# Arria10_Power.net
KiCad netlist of a schematic drawn in Altium Designer
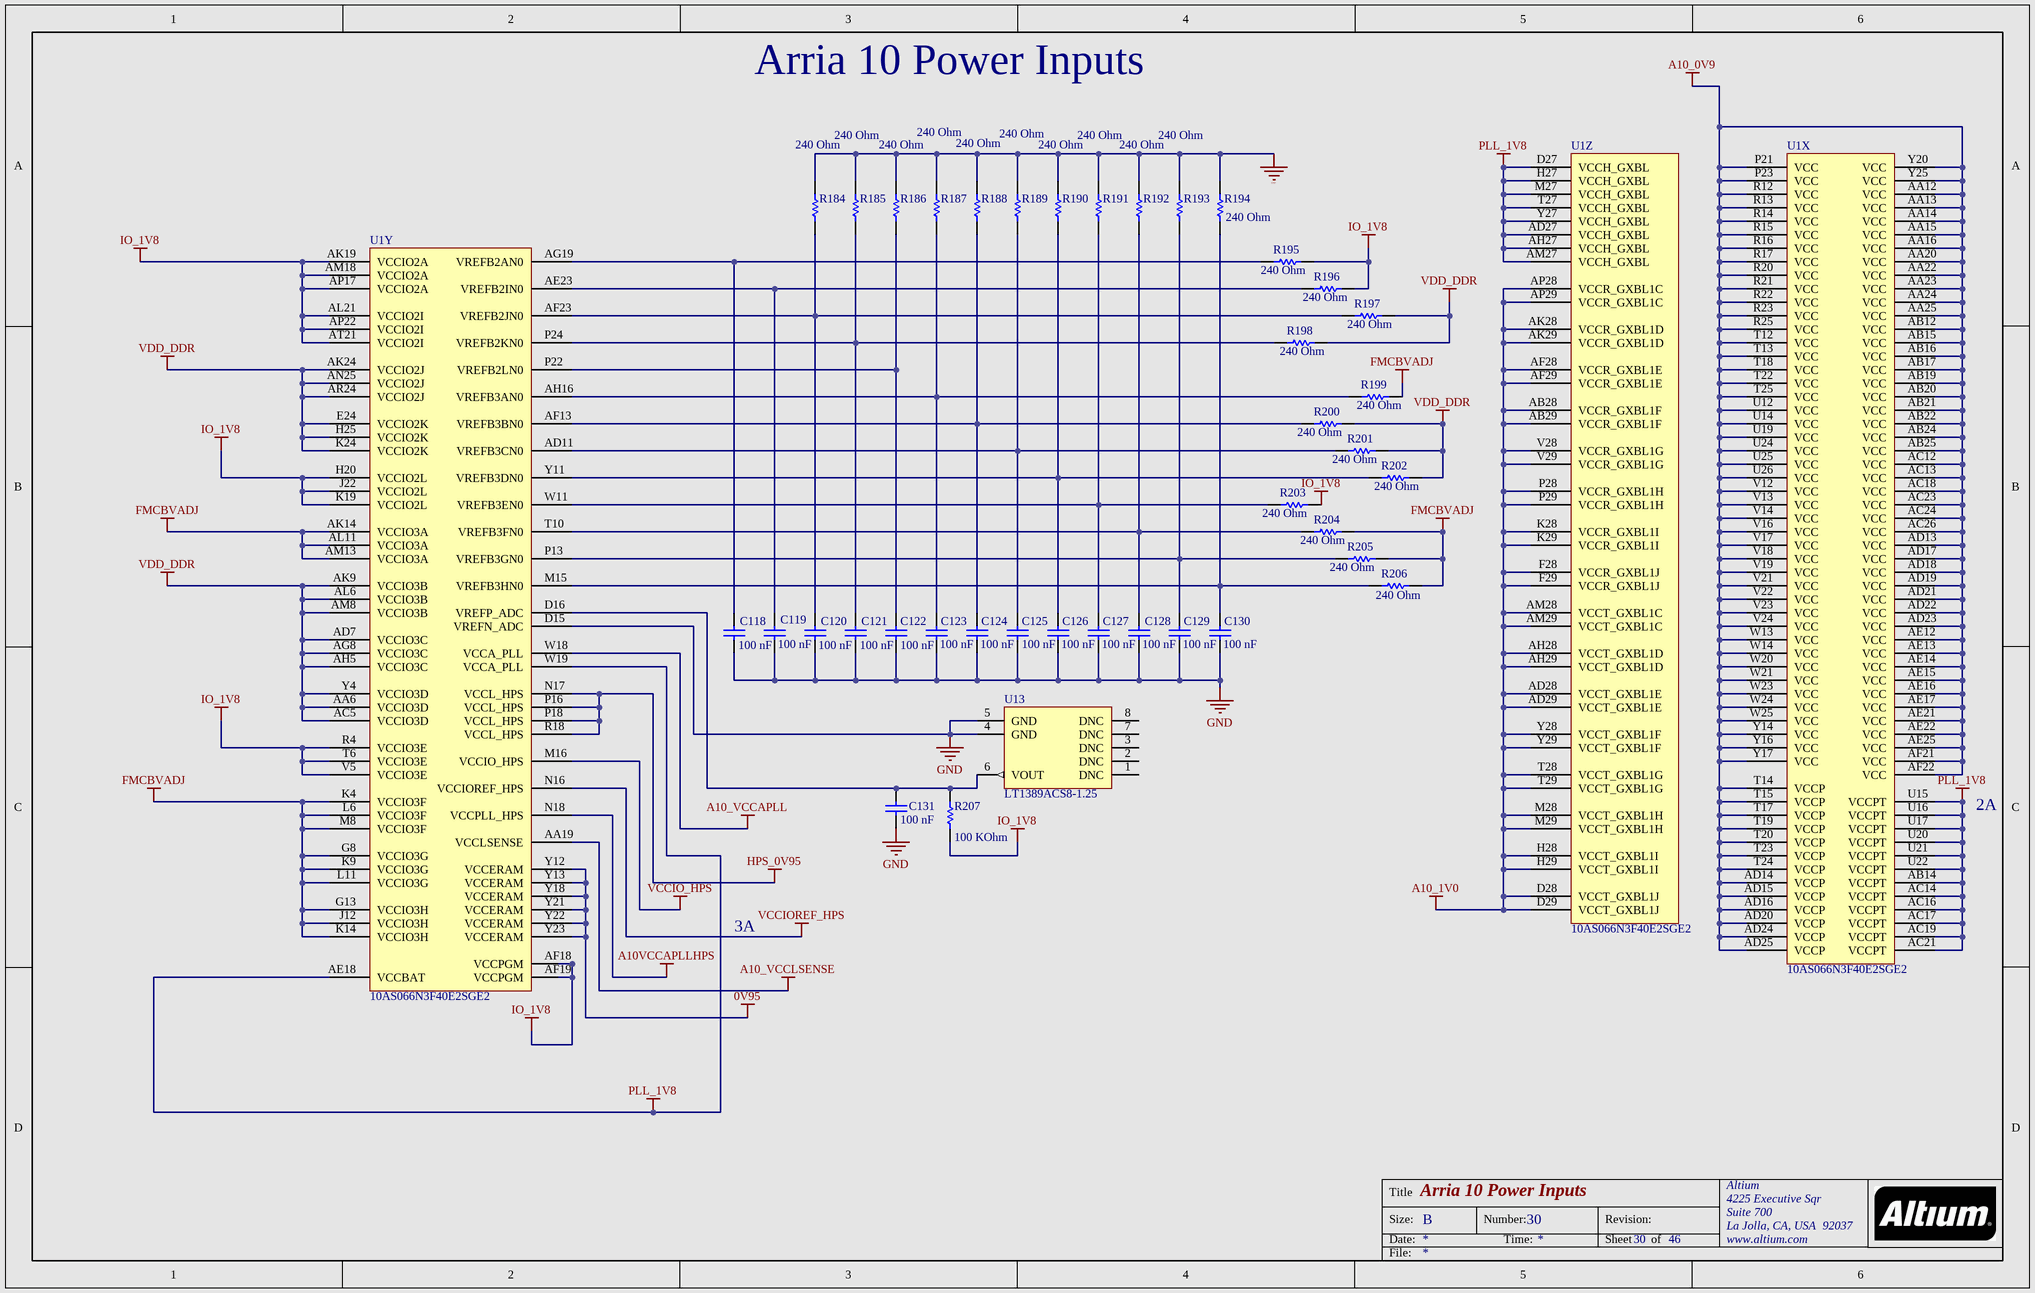
[diagram p0: Arria10_Power.SchDoc]

(export (version "E")
  (design (tool "Eeschema 10.0.6"))
  (components
    (comp (ref "C118")
      (value "GRM033R60J104KE19D")
      (footprint "CAPC0603X33X15LL03T05")
      (description "Chip Capacitor, 100 nF, +/- 10%, 6.3 V, -55 to 85 degC, 0201 (0603 Metric), RoHS, Tape and Reel")
      (fields
        (field (name "TOLERANCE") "10%")
        (field (name "CAPACITANCE") "100 nF")
        (field (name "MANUFACTURER") "Basic Passives")
      )
      (libsource (lib "Altium Content Vault") (part "CAP-NP-2"))
    )
    (comp (ref "C119")
      (value "GRM033R60J104KE19D")
      (footprint "CAPC0603X33X15LL03T05")
      (description "Chip Capacitor, 100 nF, +/- 10%, 6.3 V, -55 to 85 degC, 0201 (0603 Metric), RoHS, Tape and Reel")
      (fields
        (field (name "TOLERANCE") "10%")
        (field (name "CAPACITANCE") "100 nF")
        (field (name "MANUFACTURER") "Basic Passives")
      )
      (libsource (lib "Altium Content Vault") (part "CAP-NP-2"))
    )
    (comp (ref "C120")
      (value "GRM033R60J104KE19D")
      (footprint "CAPC0603X33X15LL03T05")
      (description "Chip Capacitor, 100 nF, +/- 10%, 6.3 V, -55 to 85 degC, 0201 (0603 Metric), RoHS, Tape and Reel")
      (fields
        (field (name "TOLERANCE") "10%")
        (field (name "CAPACITANCE") "100 nF")
        (field (name "MANUFACTURER") "Basic Passives")
      )
      (libsource (lib "Altium Content Vault") (part "CAP-NP-2"))
    )
    (comp (ref "C121")
      (value "GRM033R60J104KE19D")
      (footprint "CAPC0603X33X15LL03T05")
      (description "Chip Capacitor, 100 nF, +/- 10%, 6.3 V, -55 to 85 degC, 0201 (0603 Metric), RoHS, Tape and Reel")
      (fields
        (field (name "TOLERANCE") "10%")
        (field (name "CAPACITANCE") "100 nF")
        (field (name "MANUFACTURER") "Basic Passives")
      )
      (libsource (lib "Altium Content Vault") (part "CAP-NP-2"))
    )
    (comp (ref "C122")
      (value "GRM033R60J104KE19D")
      (footprint "CAPC0603X33X15LL03T05")
      (description "Chip Capacitor, 100 nF, +/- 10%, 6.3 V, -55 to 85 degC, 0201 (0603 Metric), RoHS, Tape and Reel")
      (fields
        (field (name "TOLERANCE") "10%")
        (field (name "CAPACITANCE") "100 nF")
        (field (name "MANUFACTURER") "Basic Passives")
      )
      (libsource (lib "Altium Content Vault") (part "CAP-NP-2"))
    )
    (comp (ref "C123")
      (value "GRM033R60J104KE19D")
      (footprint "CAPC0603X33X15LL03T05")
      (description "Chip Capacitor, 100 nF, +/- 10%, 6.3 V, -55 to 85 degC, 0201 (0603 Metric), RoHS, Tape and Reel")
      (fields
        (field (name "TOLERANCE") "10%")
        (field (name "CAPACITANCE") "100 nF")
        (field (name "MANUFACTURER") "Basic Passives")
      )
      (libsource (lib "Altium Content Vault") (part "CAP-NP-2"))
    )
    (comp (ref "C124")
      (value "GRM033R60J104KE19D")
      (footprint "CAPC0603X33X15LL03T05")
      (description "Chip Capacitor, 100 nF, +/- 10%, 6.3 V, -55 to 85 degC, 0201 (0603 Metric), RoHS, Tape and Reel")
      (fields
        (field (name "TOLERANCE") "10%")
        (field (name "CAPACITANCE") "100 nF")
        (field (name "MANUFACTURER") "Basic Passives")
      )
      (libsource (lib "Altium Content Vault") (part "CAP-NP-2"))
    )
    (comp (ref "C125")
      (value "GRM033R60J104KE19D")
      (footprint "CAPC0603X33X15LL03T05")
      (description "Chip Capacitor, 100 nF, +/- 10%, 6.3 V, -55 to 85 degC, 0201 (0603 Metric), RoHS, Tape and Reel")
      (fields
        (field (name "TOLERANCE") "10%")
        (field (name "CAPACITANCE") "100 nF")
        (field (name "MANUFACTURER") "Basic Passives")
      )
      (libsource (lib "Altium Content Vault") (part "CAP-NP-2"))
    )
    (comp (ref "C126")
      (value "GRM033R60J104KE19D")
      (footprint "CAPC0603X33X15LL03T05")
      (description "Chip Capacitor, 100 nF, +/- 10%, 6.3 V, -55 to 85 degC, 0201 (0603 Metric), RoHS, Tape and Reel")
      (fields
        (field (name "TOLERANCE") "10%")
        (field (name "CAPACITANCE") "100 nF")
        (field (name "MANUFACTURER") "Basic Passives")
      )
      (libsource (lib "Altium Content Vault") (part "CAP-NP-2"))
    )
    (comp (ref "C127")
      (value "GRM033R60J104KE19D")
      (footprint "CAPC0603X33X15LL03T05")
      (description "Chip Capacitor, 100 nF, +/- 10%, 6.3 V, -55 to 85 degC, 0201 (0603 Metric), RoHS, Tape and Reel")
      (fields
        (field (name "TOLERANCE") "10%")
        (field (name "CAPACITANCE") "100 nF")
        (field (name "MANUFACTURER") "Basic Passives")
      )
      (libsource (lib "Altium Content Vault") (part "CAP-NP-2"))
    )
    (comp (ref "C128")
      (value "GRM033R60J104KE19D")
      (footprint "CAPC0603X33X15LL03T05")
      (description "Chip Capacitor, 100 nF, +/- 10%, 6.3 V, -55 to 85 degC, 0201 (0603 Metric), RoHS, Tape and Reel")
      (fields
        (field (name "TOLERANCE") "10%")
        (field (name "CAPACITANCE") "100 nF")
        (field (name "MANUFACTURER") "Basic Passives")
      )
      (libsource (lib "Altium Content Vault") (part "CAP-NP-2"))
    )
    (comp (ref "C129")
      (value "GRM033R60J104KE19D")
      (footprint "CAPC0603X33X15LL03T05")
      (description "Chip Capacitor, 100 nF, +/- 10%, 6.3 V, -55 to 85 degC, 0201 (0603 Metric), RoHS, Tape and Reel")
      (fields
        (field (name "TOLERANCE") "10%")
        (field (name "CAPACITANCE") "100 nF")
        (field (name "MANUFACTURER") "Basic Passives")
      )
      (libsource (lib "Altium Content Vault") (part "CAP-NP-2"))
    )
    (comp (ref "C130")
      (value "GRM033R60J104KE19D")
      (footprint "CAPC0603X33X15LL03T05")
      (description "Chip Capacitor, 100 nF, +/- 10%, 6.3 V, -55 to 85 degC, 0201 (0603 Metric), RoHS, Tape and Reel")
      (fields
        (field (name "TOLERANCE") "10%")
        (field (name "CAPACITANCE") "100 nF")
        (field (name "MANUFACTURER") "Basic Passives")
      )
      (libsource (lib "Altium Content Vault") (part "CAP-NP-2"))
    )
    (comp (ref "C131")
      (value "C1005X7R1E104M")
      (footprint "CAPC1005X55X10LL05")
      (description "Chip Capacitor, 0.1 uF, +/- 20%, 25 V, -55 to 125 degC, 0402 (1005 Metric), RoHS, Tape and Reel")
      (fields (field (name "TOLERANCE") "20%") (field (name "CAPACITANCE") "100 nF"))
      (libsource (lib "Altium Content Vault") (part "CAP-NP-2"))
    )
    (comp (ref "R184")
      (value "ERJ-2GEJ241x")
      (footprint "RESC1005X40X25ML05T05")
      (description "Chip Resistor, 240 Ohm, +/- 5%, 100 mW, -55 to 155 degC, 0402 (1005 Metric), RoHS, Tape and Reel")
      (fields
        (field (name "TOLERANCE") "5%")
        (field (name "RESISTANCE") "240 Ohm")
        (field (name "MANUFACTURER") "Basic Passives")
      )
      (libsource (lib "Altium Content Vault") (part "RES-2"))
    )
    (comp (ref "R185")
      (value "ERJ-2GEJ241x")
      (footprint "RESC1005X40X25ML05T05")
      (description "Chip Resistor, 240 Ohm, +/- 5%, 100 mW, -55 to 155 degC, 0402 (1005 Metric), RoHS, Tape and Reel")
      (fields
        (field (name "TOLERANCE") "5%")
        (field (name "RESISTANCE") "240 Ohm")
        (field (name "MANUFACTURER") "Basic Passives")
      )
      (libsource (lib "Altium Content Vault") (part "RES-2"))
    )
    (comp (ref "R186")
      (value "ERJ-2GEJ241x")
      (footprint "RESC1005X40X25ML05T05")
      (description "Chip Resistor, 240 Ohm, +/- 5%, 100 mW, -55 to 155 degC, 0402 (1005 Metric), RoHS, Tape and Reel")
      (fields
        (field (name "TOLERANCE") "5%")
        (field (name "RESISTANCE") "240 Ohm")
        (field (name "MANUFACTURER") "Basic Passives")
      )
      (libsource (lib "Altium Content Vault") (part "RES-2"))
    )
    (comp (ref "R187")
      (value "ERJ-2GEJ241x")
      (footprint "RESC1005X40X25ML05T05")
      (description "Chip Resistor, 240 Ohm, +/- 5%, 100 mW, -55 to 155 degC, 0402 (1005 Metric), RoHS, Tape and Reel")
      (fields
        (field (name "TOLERANCE") "5%")
        (field (name "RESISTANCE") "240 Ohm")
        (field (name "MANUFACTURER") "Basic Passives")
      )
      (libsource (lib "Altium Content Vault") (part "RES-2"))
    )
    (comp (ref "R188")
      (value "ERJ-2GEJ241x")
      (footprint "RESC1005X40X25ML05T05")
      (description "Chip Resistor, 240 Ohm, +/- 5%, 100 mW, -55 to 155 degC, 0402 (1005 Metric), RoHS, Tape and Reel")
      (fields
        (field (name "TOLERANCE") "5%")
        (field (name "RESISTANCE") "240 Ohm")
        (field (name "MANUFACTURER") "Basic Passives")
      )
      (libsource (lib "Altium Content Vault") (part "RES-2"))
    )
    (comp (ref "R189")
      (value "ERJ-2GEJ241x")
      (footprint "RESC1005X40X25ML05T05")
      (description "Chip Resistor, 240 Ohm, +/- 5%, 100 mW, -55 to 155 degC, 0402 (1005 Metric), RoHS, Tape and Reel")
      (fields
        (field (name "TOLERANCE") "5%")
        (field (name "RESISTANCE") "240 Ohm")
        (field (name "MANUFACTURER") "Basic Passives")
      )
      (libsource (lib "Altium Content Vault") (part "RES-2"))
    )
    (comp (ref "R190")
      (value "ERJ-2GEJ241x")
      (footprint "RESC1005X40X25ML05T05")
      (description "Chip Resistor, 240 Ohm, +/- 5%, 100 mW, -55 to 155 degC, 0402 (1005 Metric), RoHS, Tape and Reel")
      (fields
        (field (name "TOLERANCE") "5%")
        (field (name "RESISTANCE") "240 Ohm")
        (field (name "MANUFACTURER") "Basic Passives")
      )
      (libsource (lib "Altium Content Vault") (part "RES-2"))
    )
    (comp (ref "R191")
      (value "ERJ-2GEJ241x")
      (footprint "RESC1005X40X25ML05T05")
      (description "Chip Resistor, 240 Ohm, +/- 5%, 100 mW, -55 to 155 degC, 0402 (1005 Metric), RoHS, Tape and Reel")
      (fields
        (field (name "TOLERANCE") "5%")
        (field (name "RESISTANCE") "240 Ohm")
        (field (name "MANUFACTURER") "Basic Passives")
      )
      (libsource (lib "Altium Content Vault") (part "RES-2"))
    )
    (comp (ref "R192")
      (value "ERJ-2GEJ241x")
      (footprint "RESC1005X40X25ML05T05")
      (description "Chip Resistor, 240 Ohm, +/- 5%, 100 mW, -55 to 155 degC, 0402 (1005 Metric), RoHS, Tape and Reel")
      (fields
        (field (name "TOLERANCE") "5%")
        (field (name "RESISTANCE") "240 Ohm")
        (field (name "MANUFACTURER") "Basic Passives")
      )
      (libsource (lib "Altium Content Vault") (part "RES-2"))
    )
    (comp (ref "R193")
      (value "ERJ-2GEJ241x")
      (footprint "RESC1005X40X25ML05T05")
      (description "Chip Resistor, 240 Ohm, +/- 5%, 100 mW, -55 to 155 degC, 0402 (1005 Metric), RoHS, Tape and Reel")
      (fields
        (field (name "TOLERANCE") "5%")
        (field (name "RESISTANCE") "240 Ohm")
        (field (name "MANUFACTURER") "Basic Passives")
      )
      (libsource (lib "Altium Content Vault") (part "RES-2"))
    )
    (comp (ref "R194")
      (value "ERJ-2GEJ241x")
      (footprint "RESC1005X40X25ML05T05")
      (description "Chip Resistor, 240 Ohm, +/- 5%, 100 mW, -55 to 155 degC, 0402 (1005 Metric), RoHS, Tape and Reel")
      (fields
        (field (name "TOLERANCE") "5%")
        (field (name "RESISTANCE") "240 Ohm")
        (field (name "MANUFACTURER") "Basic Passives")
      )
      (libsource (lib "Altium Content Vault") (part "RES-2"))
    )
    (comp (ref "R195")
      (value "ERJ-2GEJ241x")
      (footprint "RESC1005X40X25ML05T05")
      (description "Chip Resistor, 240 Ohm, +/- 5%, 100 mW, -55 to 155 degC, 0402 (1005 Metric), RoHS, Tape and Reel")
      (fields
        (field (name "TOLERANCE") "5%")
        (field (name "RESISTANCE") "240 Ohm")
        (field (name "MANUFACTURER") "Basic Passives")
      )
      (libsource (lib "Altium Content Vault") (part "RES-2"))
    )
    (comp (ref "R196")
      (value "ERJ-2GEJ241x")
      (footprint "RESC1005X40X25ML05T05")
      (description "Chip Resistor, 240 Ohm, +/- 5%, 100 mW, -55 to 155 degC, 0402 (1005 Metric), RoHS, Tape and Reel")
      (fields
        (field (name "TOLERANCE") "5%")
        (field (name "RESISTANCE") "240 Ohm")
        (field (name "MANUFACTURER") "Basic Passives")
      )
      (libsource (lib "Altium Content Vault") (part "RES-2"))
    )
    (comp (ref "R197")
      (value "ERJ-2GEJ241x")
      (footprint "RESC1005X40X25ML05T05")
      (description "Chip Resistor, 240 Ohm, +/- 5%, 100 mW, -55 to 155 degC, 0402 (1005 Metric), RoHS, Tape and Reel")
      (fields
        (field (name "TOLERANCE") "5%")
        (field (name "RESISTANCE") "240 Ohm")
        (field (name "MANUFACTURER") "Basic Passives")
      )
      (libsource (lib "Altium Content Vault") (part "RES-2"))
    )
    (comp (ref "R198")
      (value "ERJ-2GEJ241x")
      (footprint "RESC1005X40X25ML05T05")
      (description "Chip Resistor, 240 Ohm, +/- 5%, 100 mW, -55 to 155 degC, 0402 (1005 Metric), RoHS, Tape and Reel")
      (fields
        (field (name "TOLERANCE") "5%")
        (field (name "RESISTANCE") "240 Ohm")
        (field (name "MANUFACTURER") "Basic Passives")
      )
      (libsource (lib "Altium Content Vault") (part "RES-2"))
    )
    (comp (ref "R199")
      (value "ERJ-2GEJ241x")
      (footprint "RESC1005X40X25ML05T05")
      (description "Chip Resistor, 240 Ohm, +/- 5%, 100 mW, -55 to 155 degC, 0402 (1005 Metric), RoHS, Tape and Reel")
      (fields
        (field (name "TOLERANCE") "5%")
        (field (name "RESISTANCE") "240 Ohm")
        (field (name "MANUFACTURER") "Basic Passives")
      )
      (libsource (lib "Altium Content Vault") (part "RES-2"))
    )
    (comp (ref "R200")
      (value "ERJ-2GEJ241x")
      (footprint "RESC1005X40X25ML05T05")
      (description "Chip Resistor, 240 Ohm, +/- 5%, 100 mW, -55 to 155 degC, 0402 (1005 Metric), RoHS, Tape and Reel")
      (fields
        (field (name "TOLERANCE") "5%")
        (field (name "RESISTANCE") "240 Ohm")
        (field (name "MANUFACTURER") "Basic Passives")
      )
      (libsource (lib "Altium Content Vault") (part "RES-2"))
    )
    (comp (ref "R201")
      (value "ERJ-2GEJ241x")
      (footprint "RESC1005X40X25ML05T05")
      (description "Chip Resistor, 240 Ohm, +/- 5%, 100 mW, -55 to 155 degC, 0402 (1005 Metric), RoHS, Tape and Reel")
      (fields
        (field (name "TOLERANCE") "5%")
        (field (name "RESISTANCE") "240 Ohm")
        (field (name "MANUFACTURER") "Basic Passives")
      )
      (libsource (lib "Altium Content Vault") (part "RES-2"))
    )
    (comp (ref "R202")
      (value "ERJ-2GEJ241x")
      (footprint "RESC1005X40X25ML05T05")
      (description "Chip Resistor, 240 Ohm, +/- 5%, 100 mW, -55 to 155 degC, 0402 (1005 Metric), RoHS, Tape and Reel")
      (fields
        (field (name "TOLERANCE") "5%")
        (field (name "RESISTANCE") "240 Ohm")
        (field (name "MANUFACTURER") "Basic Passives")
      )
      (libsource (lib "Altium Content Vault") (part "RES-2"))
    )
    (comp (ref "R203")
      (value "ERJ-2GEJ241x")
      (footprint "RESC1005X40X25ML05T05")
      (description "Chip Resistor, 240 Ohm, +/- 5%, 100 mW, -55 to 155 degC, 0402 (1005 Metric), RoHS, Tape and Reel")
      (fields
        (field (name "TOLERANCE") "5%")
        (field (name "RESISTANCE") "240 Ohm")
        (field (name "MANUFACTURER") "Basic Passives")
      )
      (libsource (lib "Altium Content Vault") (part "RES-2"))
    )
    (comp (ref "R204")
      (value "ERJ-2GEJ241x")
      (footprint "RESC1005X40X25ML05T05")
      (description "Chip Resistor, 240 Ohm, +/- 5%, 100 mW, -55 to 155 degC, 0402 (1005 Metric), RoHS, Tape and Reel")
      (fields
        (field (name "TOLERANCE") "5%")
        (field (name "RESISTANCE") "240 Ohm")
        (field (name "MANUFACTURER") "Basic Passives")
      )
      (libsource (lib "Altium Content Vault") (part "RES-2"))
    )
    (comp (ref "R205")
      (value "ERJ-2GEJ241x")
      (footprint "RESC1005X40X25ML05T05")
      (description "Chip Resistor, 240 Ohm, +/- 5%, 100 mW, -55 to 155 degC, 0402 (1005 Metric), RoHS, Tape and Reel")
      (fields
        (field (name "TOLERANCE") "5%")
        (field (name "RESISTANCE") "240 Ohm")
        (field (name "MANUFACTURER") "Basic Passives")
      )
      (libsource (lib "Altium Content Vault") (part "RES-2"))
    )
    (comp (ref "R206")
      (value "ERJ-2GEJ241x")
      (footprint "RESC1005X40X25ML05T05")
      (description "Chip Resistor, 240 Ohm, +/- 5%, 100 mW, -55 to 155 degC, 0402 (1005 Metric), RoHS, Tape and Reel")
      (fields
        (field (name "TOLERANCE") "5%")
        (field (name "RESISTANCE") "240 Ohm")
        (field (name "MANUFACTURER") "Basic Passives")
      )
      (libsource (lib "Altium Content Vault") (part "RES-2"))
    )
    (comp (ref "R207")
      (value "ERJ-2RKF1003X")
      (footprint "RESC1005X40X25LL05T05")
      (description "Chip Resistor, 100 KOhm, +/- 1%, 100 mW, -55 to 155 degC, 0402 (1005 Metric), RoHS, Tape and Reel")
      (fields
        (field (name "TOLERANCE") "1%")
        (field (name "RESISTANCE") "100 KOhm")
        (field (name "MANUFACTURER") "Basic Passives")
      )
      (libsource (lib "Altium Content Vault") (part "RES-2"))
    )
    (comp (ref "U1")
      (value "10AS066N3F40E2SGE2")
      (footprint "ALTR-FBGA1517_A-350")
      (libsource (lib "Altium Content Vault") (part "ALTR-10AS066NF40-FBGA1517"))
    )
    (comp (ref "U13")
      (value "LT1389ACS8-1.25")
      (footprint "LT-S8-8_M")
      (fields (field (name "TOLERANCE") "±0.05%"))
      (libsource (lib "Altium Content Vault") (part "LT-LT1389XXXX-S8-8"))
    )
  )
  (nets
    (net (code "1") (name "0V95") (class "Default")
      (node (ref "U1") (pin "Y12") (pinfunction "VCCERAM_Y12") (pintype "power_in"))
      (node (ref "U1") (pin "Y13") (pinfunction "VCCERAM_Y13") (pintype "power_in"))
      (node (ref "U1") (pin "Y18") (pinfunction "VCCERAM_Y18") (pintype "power_in"))
      (node (ref "U1") (pin "Y21") (pinfunction "VCCERAM_Y21") (pintype "power_in"))
      (node (ref "U1") (pin "Y22") (pinfunction "VCCERAM_Y22") (pintype "power_in"))
      (node (ref "U1") (pin "Y23") (pinfunction "VCCERAM_Y23") (pintype "power_in"))
    )
    (net (code "2") (name "A10VCCAPLLHPS") (class "Default")
      (node (ref "U1") (pin "N18") (pinfunction "VCCPLL_HPS_N18") (pintype "power_in"))
    )
    (net (code "3") (name "A10_0V9") (class "Default")
      (node (ref "U1") (pin "AA12") (pinfunction "VCC_AA12") (pintype "power_in"))
      (node (ref "U1") (pin "AA13") (pinfunction "VCC_AA13") (pintype "power_in"))
      (node (ref "U1") (pin "AA14") (pinfunction "VCC_AA14") (pintype "power_in"))
      (node (ref "U1") (pin "AA15") (pinfunction "VCC_AA15") (pintype "power_in"))
      (node (ref "U1") (pin "AA16") (pinfunction "VCC_AA16") (pintype "power_in"))
      (node (ref "U1") (pin "AA20") (pinfunction "VCC_AA20") (pintype "power_in"))
      (node (ref "U1") (pin "AA22") (pinfunction "VCC_AA22") (pintype "power_in"))
      (node (ref "U1") (pin "AA23") (pinfunction "VCC_AA23") (pintype "power_in"))
      (node (ref "U1") (pin "AA24") (pinfunction "VCC_AA24") (pintype "power_in"))
      (node (ref "U1") (pin "AA25") (pinfunction "VCC_AA25") (pintype "power_in"))
      (node (ref "U1") (pin "AB12") (pinfunction "VCC_AB12") (pintype "power_in"))
      (node (ref "U1") (pin "AB15") (pinfunction "VCC_AB15") (pintype "power_in"))
      (node (ref "U1") (pin "AB16") (pinfunction "VCC_AB16") (pintype "power_in"))
      (node (ref "U1") (pin "AB17") (pinfunction "VCC_AB17") (pintype "power_in"))
      (node (ref "U1") (pin "AB19") (pinfunction "VCC_AB19") (pintype "power_in"))
      (node (ref "U1") (pin "AB20") (pinfunction "VCC_AB20") (pintype "power_in"))
      (node (ref "U1") (pin "AB21") (pinfunction "VCC_AB21") (pintype "power_in"))
      (node (ref "U1") (pin "AB22") (pinfunction "VCC_AB22") (pintype "power_in"))
      (node (ref "U1") (pin "AB24") (pinfunction "VCC_AB24") (pintype "power_in"))
      (node (ref "U1") (pin "AB25") (pinfunction "VCC_AB25") (pintype "power_in"))
      (node (ref "U1") (pin "AC12") (pinfunction "VCC_AC12") (pintype "power_in"))
      (node (ref "U1") (pin "AC13") (pinfunction "VCC_AC13") (pintype "power_in"))
      (node (ref "U1") (pin "AC18") (pinfunction "VCC_AC18") (pintype "power_in"))
      (node (ref "U1") (pin "AC23") (pinfunction "VCC_AC23") (pintype "power_in"))
      (node (ref "U1") (pin "AC24") (pinfunction "VCC_AC24") (pintype "power_in"))
      (node (ref "U1") (pin "AC26") (pinfunction "VCC_AC26") (pintype "power_in"))
      (node (ref "U1") (pin "AD13") (pinfunction "VCC_AD13") (pintype "power_in"))
      (node (ref "U1") (pin "AD14") (pinfunction "VCCP_AD14") (pintype "power_in"))
      (node (ref "U1") (pin "AD15") (pinfunction "VCCP_AD15") (pintype "power_in"))
      (node (ref "U1") (pin "AD16") (pinfunction "VCCP_AD16") (pintype "power_in"))
      (node (ref "U1") (pin "AD17") (pinfunction "VCC_AD17") (pintype "power_in"))
      (node (ref "U1") (pin "AD18") (pinfunction "VCC_AD18") (pintype "power_in"))
      (node (ref "U1") (pin "AD19") (pinfunction "VCC_AD19") (pintype "power_in"))
      (node (ref "U1") (pin "AD20") (pinfunction "VCCP_AD20") (pintype "power_in"))
      (node (ref "U1") (pin "AD21") (pinfunction "VCC_AD21") (pintype "power_in"))
      (node (ref "U1") (pin "AD22") (pinfunction "VCC_AD22") (pintype "power_in"))
      (node (ref "U1") (pin "AD23") (pinfunction "VCC_AD23") (pintype "power_in"))
      (node (ref "U1") (pin "AD24") (pinfunction "VCCP_AD24") (pintype "power_in"))
      (node (ref "U1") (pin "AD25") (pinfunction "VCCP_AD25") (pintype "power_in"))
      (node (ref "U1") (pin "AE12") (pinfunction "VCC_AE12") (pintype "power_in"))
      (node (ref "U1") (pin "AE13") (pinfunction "VCC_AE13") (pintype "power_in"))
      (node (ref "U1") (pin "AE14") (pinfunction "VCC_AE14") (pintype "power_in"))
      (node (ref "U1") (pin "AE15") (pinfunction "VCC_AE15") (pintype "power_in"))
      (node (ref "U1") (pin "AE16") (pinfunction "VCC_AE16") (pintype "power_in"))
      (node (ref "U1") (pin "AE17") (pinfunction "VCC_AE17") (pintype "power_in"))
      (node (ref "U1") (pin "AE21") (pinfunction "VCC_AE21") (pintype "power_in"))
      (node (ref "U1") (pin "AE22") (pinfunction "VCC_AE22") (pintype "power_in"))
      (node (ref "U1") (pin "AE25") (pinfunction "VCC_AE25") (pintype "power_in"))
      (node (ref "U1") (pin "AF21") (pinfunction "VCC_AF21") (pintype "power_in"))
      (node (ref "U1") (pin "AF22") (pinfunction "VCC_AF22") (pintype "power_in"))
      (node (ref "U1") (pin "P21") (pinfunction "VCC_P21") (pintype "power_in"))
      (node (ref "U1") (pin "P23") (pinfunction "VCC_P23") (pintype "power_in"))
      (node (ref "U1") (pin "R12") (pinfunction "VCC_R12") (pintype "power_in"))
      (node (ref "U1") (pin "R13") (pinfunction "VCC_R13") (pintype "power_in"))
      (node (ref "U1") (pin "R14") (pinfunction "VCC_R14") (pintype "power_in"))
      (node (ref "U1") (pin "R15") (pinfunction "VCC_R15") (pintype "power_in"))
      (node (ref "U1") (pin "R16") (pinfunction "VCC_R16") (pintype "power_in"))
      (node (ref "U1") (pin "R17") (pinfunction "VCC_R17") (pintype "power_in"))
      (node (ref "U1") (pin "R20") (pinfunction "VCC_R20") (pintype "power_in"))
      (node (ref "U1") (pin "R21") (pinfunction "VCC_R21") (pintype "power_in"))
      (node (ref "U1") (pin "R22") (pinfunction "VCC_R22") (pintype "power_in"))
      (node (ref "U1") (pin "R23") (pinfunction "VCC_R23") (pintype "power_in"))
      (node (ref "U1") (pin "R25") (pinfunction "VCC_R25") (pintype "power_in"))
      (node (ref "U1") (pin "T12") (pinfunction "VCC_T12") (pintype "power_in"))
      (node (ref "U1") (pin "T13") (pinfunction "VCC_T13") (pintype "power_in"))
      (node (ref "U1") (pin "T14") (pinfunction "VCCP_T14") (pintype "power_in"))
      (node (ref "U1") (pin "T15") (pinfunction "VCCP_T15") (pintype "power_in"))
      (node (ref "U1") (pin "T17") (pinfunction "VCCP_T17") (pintype "power_in"))
      (node (ref "U1") (pin "T18") (pinfunction "VCC_T18") (pintype "power_in"))
      (node (ref "U1") (pin "T19") (pinfunction "VCCP_T19") (pintype "power_in"))
      (node (ref "U1") (pin "T20") (pinfunction "VCCP_T20") (pintype "power_in"))
      (node (ref "U1") (pin "T22") (pinfunction "VCC_T22") (pintype "power_in"))
      (node (ref "U1") (pin "T23") (pinfunction "VCCP_T23") (pintype "power_in"))
      (node (ref "U1") (pin "T24") (pinfunction "VCCP_T24") (pintype "power_in"))
      (node (ref "U1") (pin "T25") (pinfunction "VCC_T25") (pintype "power_in"))
      (node (ref "U1") (pin "U12") (pinfunction "VCC_U12") (pintype "power_in"))
      (node (ref "U1") (pin "U14") (pinfunction "VCC_U14") (pintype "power_in"))
      (node (ref "U1") (pin "U19") (pinfunction "VCC_U19") (pintype "power_in"))
      (node (ref "U1") (pin "U24") (pinfunction "VCC_U24") (pintype "power_in"))
      (node (ref "U1") (pin "U25") (pinfunction "VCC_U25") (pintype "power_in"))
      (node (ref "U1") (pin "U26") (pinfunction "VCC_U26") (pintype "power_in"))
      (node (ref "U1") (pin "V12") (pinfunction "VCC_V12") (pintype "power_in"))
      (node (ref "U1") (pin "V13") (pinfunction "VCC_V13") (pintype "power_in"))
      (node (ref "U1") (pin "V14") (pinfunction "VCC_V14") (pintype "power_in"))
      (node (ref "U1") (pin "V16") (pinfunction "VCC_V16") (pintype "power_in"))
      (node (ref "U1") (pin "V17") (pinfunction "VCC_V17") (pintype "power_in"))
      (node (ref "U1") (pin "V18") (pinfunction "VCC_V18") (pintype "power_in"))
      (node (ref "U1") (pin "V19") (pinfunction "VCC_V19") (pintype "power_in"))
      (node (ref "U1") (pin "V21") (pinfunction "VCC_V21") (pintype "power_in"))
      (node (ref "U1") (pin "V22") (pinfunction "VCC_V22") (pintype "power_in"))
      (node (ref "U1") (pin "V23") (pinfunction "VCC_V23") (pintype "power_in"))
      (node (ref "U1") (pin "V24") (pinfunction "VCC_V24") (pintype "power_in"))
      (node (ref "U1") (pin "W13") (pinfunction "VCC_W13") (pintype "power_in"))
      (node (ref "U1") (pin "W14") (pinfunction "VCC_W14") (pintype "power_in"))
      (node (ref "U1") (pin "W20") (pinfunction "VCC_W20") (pintype "power_in"))
      (node (ref "U1") (pin "W21") (pinfunction "VCC_W21") (pintype "power_in"))
      (node (ref "U1") (pin "W23") (pinfunction "VCC_W23") (pintype "power_in"))
      (node (ref "U1") (pin "W24") (pinfunction "VCC_W24") (pintype "power_in"))
      (node (ref "U1") (pin "W25") (pinfunction "VCC_W25") (pintype "power_in"))
      (node (ref "U1") (pin "Y14") (pinfunction "VCC_Y14") (pintype "power_in"))
      (node (ref "U1") (pin "Y16") (pinfunction "VCC_Y16") (pintype "power_in"))
      (node (ref "U1") (pin "Y17") (pinfunction "VCC_Y17") (pintype "power_in"))
      (node (ref "U1") (pin "Y20") (pinfunction "VCC_Y20") (pintype "power_in"))
      (node (ref "U1") (pin "Y25") (pinfunction "VCC_Y25") (pintype "power_in"))
    )
    (net (code "4") (name "A10_1V0") (class "Default")
      (node (ref "U1") (pin "AB28") (pinfunction "VCCR_GXBL1F_AB28") (pintype "power_in"))
      (node (ref "U1") (pin "AB29") (pinfunction "VCCR_GXBL1F_AB29") (pintype "power_in"))
      (node (ref "U1") (pin "AD28") (pinfunction "VCCT_GXBL1E_AD28") (pintype "power_in"))
      (node (ref "U1") (pin "AD29") (pinfunction "VCCT_GXBL1E_AD29") (pintype "power_in"))
      (node (ref "U1") (pin "AF28") (pinfunction "VCCR_GXBL1E_AF28") (pintype "power_in"))
      (node (ref "U1") (pin "AF29") (pinfunction "VCCR_GXBL1E_AF29") (pintype "power_in"))
      (node (ref "U1") (pin "AH28") (pinfunction "VCCT_GXBL1D_AH28") (pintype "power_in"))
      (node (ref "U1") (pin "AH29") (pinfunction "VCCT_GXBL1D_AH29") (pintype "power_in"))
      (node (ref "U1") (pin "AK28") (pinfunction "VCCR_GXBL1D_AK28") (pintype "power_in"))
      (node (ref "U1") (pin "AK29") (pinfunction "VCCR_GXBL1D_AK29") (pintype "power_in"))
      (node (ref "U1") (pin "AM28") (pinfunction "VCCT_GXBL1C_AM28") (pintype "power_in"))
      (node (ref "U1") (pin "AM29") (pinfunction "VCCT_GXBL1C_AM29") (pintype "power_in"))
      (node (ref "U1") (pin "AP28") (pinfunction "VCCR_GXBL1C_AP28") (pintype "power_in"))
      (node (ref "U1") (pin "AP29") (pinfunction "VCCR_GXBL1C_AP29") (pintype "power_in"))
      (node (ref "U1") (pin "D28") (pinfunction "VCCT_GXBL1J_D28") (pintype "power_in"))
      (node (ref "U1") (pin "D29") (pinfunction "VCCT_GXBL1J_D29") (pintype "power_in"))
      (node (ref "U1") (pin "F28") (pinfunction "VCCR_GXBL1J_F28") (pintype "power_in"))
      (node (ref "U1") (pin "F29") (pinfunction "VCCR_GXBL1J_F29") (pintype "power_in"))
      (node (ref "U1") (pin "H28") (pinfunction "VCCT_GXBL1I_H28") (pintype "power_in"))
      (node (ref "U1") (pin "H29") (pinfunction "VCCT_GXBL1I_H29") (pintype "power_in"))
      (node (ref "U1") (pin "K28") (pinfunction "VCCR_GXBL1I_K28") (pintype "power_in"))
      (node (ref "U1") (pin "K29") (pinfunction "VCCR_GXBL1I_K29") (pintype "power_in"))
      (node (ref "U1") (pin "M28") (pinfunction "VCCT_GXBL1H_M28") (pintype "power_in"))
      (node (ref "U1") (pin "M29") (pinfunction "VCCT_GXBL1H_M29") (pintype "power_in"))
      (node (ref "U1") (pin "P28") (pinfunction "VCCR_GXBL1H_P28") (pintype "power_in"))
      (node (ref "U1") (pin "P29") (pinfunction "VCCR_GXBL1H_P29") (pintype "power_in"))
      (node (ref "U1") (pin "T28") (pinfunction "VCCT_GXBL1G_T28") (pintype "power_in"))
      (node (ref "U1") (pin "T29") (pinfunction "VCCT_GXBL1G_T29") (pintype "power_in"))
      (node (ref "U1") (pin "V28") (pinfunction "VCCR_GXBL1G_V28") (pintype "power_in"))
      (node (ref "U1") (pin "V29") (pinfunction "VCCR_GXBL1G_V29") (pintype "power_in"))
      (node (ref "U1") (pin "Y28") (pinfunction "VCCT_GXBL1F_Y28") (pintype "power_in"))
      (node (ref "U1") (pin "Y29") (pinfunction "VCCT_GXBL1F_Y29") (pintype "power_in"))
    )
    (net (code "5") (name "A10_VCCAPLL") (class "Default")
      (node (ref "U1") (pin "W18") (pinfunction "VCCA_PLL_W18") (pintype "power_in"))
    )
    (net (code "6") (name "A10_VCCLSENSE") (class "Default")
      (node (ref "U1") (pin "AA19") (pinfunction "VCCLSENSE_AA19") (pintype "power_in"))
    )
    (net (code "7") (name "FMCBVADJ") (class "Default")
      (node (ref "R199") (pin "1") (pinfunction "1_1") (pintype "passive"))
      (node (ref "R204") (pin "1") (pinfunction "1_1") (pintype "passive"))
      (node (ref "R205") (pin "1") (pinfunction "1_1") (pintype "passive"))
      (node (ref "R206") (pin "1") (pinfunction "1_1") (pintype "passive"))
      (node (ref "U1") (pin "AK14") (pinfunction "VCCIO3A_AK14") (pintype "power_in"))
      (node (ref "U1") (pin "AL11") (pinfunction "VCCIO3A_AL11") (pintype "power_in"))
      (node (ref "U1") (pin "AM13") (pinfunction "VCCIO3A_AM13") (pintype "power_in"))
      (node (ref "U1") (pin "G13") (pinfunction "VCCIO3H_G13") (pintype "power_in"))
      (node (ref "U1") (pin "G8") (pinfunction "VCCIO3G_G8") (pintype "power_in"))
      (node (ref "U1") (pin "J12") (pinfunction "VCCIO3H_J12") (pintype "power_in"))
      (node (ref "U1") (pin "K14") (pinfunction "VCCIO3H_K14") (pintype "power_in"))
      (node (ref "U1") (pin "K4") (pinfunction "VCCIO3F_K4") (pintype "power_in"))
      (node (ref "U1") (pin "K9") (pinfunction "VCCIO3G_K9") (pintype "power_in"))
      (node (ref "U1") (pin "L11") (pinfunction "VCCIO3G_L11") (pintype "power_in"))
      (node (ref "U1") (pin "L6") (pinfunction "VCCIO3F_L6") (pintype "power_in"))
      (node (ref "U1") (pin "M8") (pinfunction "VCCIO3F_M8") (pintype "power_in"))
    )
    (net (code "8") (name "GND") (class "Default")
      (node (ref "C118") (pin "1") (pinfunction "1_1") (pintype "passive"))
      (node (ref "C119") (pin "1") (pinfunction "1_1") (pintype "passive"))
      (node (ref "C120") (pin "1") (pinfunction "1_1") (pintype "passive"))
      (node (ref "C121") (pin "1") (pinfunction "1_1") (pintype "passive"))
      (node (ref "C122") (pin "1") (pinfunction "1_1") (pintype "passive"))
      (node (ref "C123") (pin "1") (pinfunction "1_1") (pintype "passive"))
      (node (ref "C124") (pin "1") (pinfunction "1_1") (pintype "passive"))
      (node (ref "C125") (pin "1") (pinfunction "1_1") (pintype "passive"))
      (node (ref "C126") (pin "1") (pinfunction "1_1") (pintype "passive"))
      (node (ref "C127") (pin "1") (pinfunction "1_1") (pintype "passive"))
      (node (ref "C128") (pin "1") (pinfunction "1_1") (pintype "passive"))
      (node (ref "C129") (pin "1") (pinfunction "1_1") (pintype "passive"))
      (node (ref "C130") (pin "1") (pinfunction "1_1") (pintype "passive"))
      (node (ref "C131") (pin "1") (pinfunction "1_1") (pintype "passive"))
      (node (ref "R184") (pin "2") (pinfunction "2_2") (pintype "passive"))
      (node (ref "R185") (pin "2") (pinfunction "2_2") (pintype "passive"))
      (node (ref "R186") (pin "2") (pinfunction "2_2") (pintype "passive"))
      (node (ref "R187") (pin "2") (pinfunction "2_2") (pintype "passive"))
      (node (ref "R188") (pin "2") (pinfunction "2_2") (pintype "passive"))
      (node (ref "R189") (pin "2") (pinfunction "2_2") (pintype "passive"))
      (node (ref "R190") (pin "2") (pinfunction "2_2") (pintype "passive"))
      (node (ref "R191") (pin "2") (pinfunction "2_2") (pintype "passive"))
      (node (ref "R192") (pin "2") (pinfunction "2_2") (pintype "passive"))
      (node (ref "R193") (pin "2") (pinfunction "2_2") (pintype "passive"))
      (node (ref "R194") (pin "1") (pinfunction "1_1") (pintype "passive"))
      (node (ref "U1") (pin "D15") (pinfunction "VREFN_ADC_D15") (pintype "power_in"))
      (node (ref "U13") (pin "4") (pinfunction "GND_4") (pintype "power_in"))
      (node (ref "U13") (pin "5") (pinfunction "GND_5") (pintype "power_in"))
    )
    (net (code "9") (name "HPS_0V95") (class "Default")
      (node (ref "U1") (pin "N17") (pinfunction "VCCL_HPS_N17") (pintype "power_in"))
      (node (ref "U1") (pin "P16") (pinfunction "VCCL_HPS_P16") (pintype "power_in"))
      (node (ref "U1") (pin "P18") (pinfunction "VCCL_HPS_P18") (pintype "power_in"))
      (node (ref "U1") (pin "R18") (pinfunction "VCCL_HPS_R18") (pintype "power_in"))
    )
    (net (code "10") (name "IO_1V8") (class "Default")
      (node (ref "R195") (pin "1") (pinfunction "1_1") (pintype "passive"))
      (node (ref "R196") (pin "1") (pinfunction "1_1") (pintype "passive"))
      (node (ref "R203") (pin "1") (pinfunction "1_1") (pintype "passive"))
      (node (ref "R207") (pin "1") (pinfunction "1_1") (pintype "passive"))
      (node (ref "U1") (pin "AF18") (pinfunction "VCCPGM_AF18") (pintype "power_in"))
      (node (ref "U1") (pin "AF19") (pinfunction "VCCPGM_AF19") (pintype "power_in"))
      (node (ref "U1") (pin "AK19") (pinfunction "VCCIO2A_AK19") (pintype "power_in"))
      (node (ref "U1") (pin "AL21") (pinfunction "VCCIO2I_AL21") (pintype "power_in"))
      (node (ref "U1") (pin "AM18") (pinfunction "VCCIO2A_AM18") (pintype "power_in"))
      (node (ref "U1") (pin "AP17") (pinfunction "VCCIO2A_AP17") (pintype "power_in"))
      (node (ref "U1") (pin "AP22") (pinfunction "VCCIO2I_AP22") (pintype "power_in"))
      (node (ref "U1") (pin "AT21") (pinfunction "VCCIO2I_AT21") (pintype "power_in"))
      (node (ref "U1") (pin "H20") (pinfunction "VCCIO2L_H20") (pintype "power_in"))
      (node (ref "U1") (pin "J22") (pinfunction "VCCIO2L_J22") (pintype "power_in"))
      (node (ref "U1") (pin "K19") (pinfunction "VCCIO2L_K19") (pintype "power_in"))
      (node (ref "U1") (pin "R4") (pinfunction "VCCIO3E_R4") (pintype "power_in"))
      (node (ref "U1") (pin "T6") (pinfunction "VCCIO3E_T6") (pintype "power_in"))
      (node (ref "U1") (pin "V5") (pinfunction "VCCIO3E_V5") (pintype "power_in"))
    )
    (net (code "11") (name "Net-(U1Y-VREFB2AN0)") (class "Default")
      (node (ref "C118") (pin "2") (pinfunction "2_2") (pintype "passive"))
      (node (ref "R195") (pin "2") (pinfunction "2_2") (pintype "passive"))
      (node (ref "U1") (pin "AG19") (pinfunction "VREFB2AN0_AG19") (pintype "power_in"))
    )
    (net (code "12") (name "Net-(U1Y-VREFB2IN0)") (class "Default")
      (node (ref "C119") (pin "2") (pinfunction "2_2") (pintype "passive"))
      (node (ref "R196") (pin "2") (pinfunction "2_2") (pintype "passive"))
      (node (ref "U1") (pin "AE23") (pinfunction "VREFB2IN0_AE23") (pintype "power_in"))
    )
    (net (code "13") (name "Net-(U1Y-VREFB2JN0)") (class "Default")
      (node (ref "C120") (pin "2") (pinfunction "2_2") (pintype "passive"))
      (node (ref "R184") (pin "1") (pinfunction "1_1") (pintype "passive"))
      (node (ref "R197") (pin "2") (pinfunction "2_2") (pintype "passive"))
      (node (ref "U1") (pin "AF23") (pinfunction "VREFB2JN0_AF23") (pintype "power_in"))
    )
    (net (code "14") (name "Net-(U1Y-VREFB2KN0)") (class "Default")
      (node (ref "C121") (pin "2") (pinfunction "2_2") (pintype "passive"))
      (node (ref "R185") (pin "1") (pinfunction "1_1") (pintype "passive"))
      (node (ref "R198") (pin "2") (pinfunction "2_2") (pintype "passive"))
      (node (ref "U1") (pin "P24") (pinfunction "VREFB2KN0_P24") (pintype "power_in"))
    )
    (net (code "15") (name "Net-(U1Y-VREFB2LN0)") (class "Default")
      (node (ref "C122") (pin "2") (pinfunction "2_2") (pintype "passive"))
      (node (ref "R186") (pin "1") (pinfunction "1_1") (pintype "passive"))
      (node (ref "U1") (pin "P22") (pinfunction "VREFB2LN0_P22") (pintype "power_in"))
    )
    (net (code "16") (name "Net-(U1Y-VREFB3AN0)") (class "Default")
      (node (ref "C123") (pin "2") (pinfunction "2_2") (pintype "passive"))
      (node (ref "R187") (pin "1") (pinfunction "1_1") (pintype "passive"))
      (node (ref "R199") (pin "2") (pinfunction "2_2") (pintype "passive"))
      (node (ref "U1") (pin "AH16") (pinfunction "VREFB3AN0_AH16") (pintype "power_in"))
    )
    (net (code "17") (name "Net-(U1Y-VREFB3BN0)") (class "Default")
      (node (ref "C124") (pin "2") (pinfunction "2_2") (pintype "passive"))
      (node (ref "R188") (pin "1") (pinfunction "1_1") (pintype "passive"))
      (node (ref "R200") (pin "2") (pinfunction "2_2") (pintype "passive"))
      (node (ref "U1") (pin "AF13") (pinfunction "VREFB3BN0_AF13") (pintype "power_in"))
    )
    (net (code "18") (name "Net-(U1Y-VREFB3CN0)") (class "Default")
      (node (ref "C125") (pin "2") (pinfunction "2_2") (pintype "passive"))
      (node (ref "R189") (pin "1") (pinfunction "1_1") (pintype "passive"))
      (node (ref "R201") (pin "2") (pinfunction "2_2") (pintype "passive"))
      (node (ref "U1") (pin "AD11") (pinfunction "VREFB3CN0_AD11") (pintype "power_in"))
    )
    (net (code "19") (name "Net-(U1Y-VREFB3DN0)") (class "Default")
      (node (ref "C126") (pin "2") (pinfunction "2_2") (pintype "passive"))
      (node (ref "R190") (pin "1") (pinfunction "1_1") (pintype "passive"))
      (node (ref "R202") (pin "2") (pinfunction "2_2") (pintype "passive"))
      (node (ref "U1") (pin "Y11") (pinfunction "VREFB3DN0_Y11") (pintype "power_in"))
    )
    (net (code "20") (name "Net-(U1Y-VREFB3EN0)") (class "Default")
      (node (ref "C127") (pin "2") (pinfunction "2_2") (pintype "passive"))
      (node (ref "R191") (pin "1") (pinfunction "1_1") (pintype "passive"))
      (node (ref "R203") (pin "2") (pinfunction "2_2") (pintype "passive"))
      (node (ref "U1") (pin "W11") (pinfunction "VREFB3EN0_W11") (pintype "power_in"))
    )
    (net (code "21") (name "Net-(U1Y-VREFB3FN0)") (class "Default")
      (node (ref "C128") (pin "2") (pinfunction "2_2") (pintype "passive"))
      (node (ref "R192") (pin "1") (pinfunction "1_1") (pintype "passive"))
      (node (ref "R204") (pin "2") (pinfunction "2_2") (pintype "passive"))
      (node (ref "U1") (pin "T10") (pinfunction "VREFB3FN0_T10") (pintype "power_in"))
    )
    (net (code "22") (name "Net-(U1Y-VREFB3GN0)") (class "Default")
      (node (ref "C129") (pin "2") (pinfunction "2_2") (pintype "passive"))
      (node (ref "R193") (pin "1") (pinfunction "1_1") (pintype "passive"))
      (node (ref "R205") (pin "2") (pinfunction "2_2") (pintype "passive"))
      (node (ref "U1") (pin "P13") (pinfunction "VREFB3GN0_P13") (pintype "power_in"))
    )
    (net (code "23") (name "Net-(U1Y-VREFB3HN0)") (class "Default")
      (node (ref "C130") (pin "2") (pinfunction "2_2") (pintype "passive"))
      (node (ref "R194") (pin "2") (pinfunction "2_2") (pintype "passive"))
      (node (ref "R206") (pin "2") (pinfunction "2_2") (pintype "passive"))
      (node (ref "U1") (pin "M15") (pinfunction "VREFB3HN0_M15") (pintype "power_in"))
    )
    (net (code "24") (name "Net-(U13-VOUT)") (class "Default")
      (node (ref "C131") (pin "2") (pinfunction "2_2") (pintype "passive"))
      (node (ref "R207") (pin "2") (pinfunction "2_2") (pintype "passive"))
      (node (ref "U1") (pin "D16") (pinfunction "VREFP_ADC_D16") (pintype "power_in"))
      (node (ref "U13") (pin "6") (pinfunction "VOUT_6") (pintype "output"))
    )
    (net (code "25") (name "PLL_1V8") (class "Default")
      (node (ref "U1") (pin "AB14") (pinfunction "VCCPT_AB14") (pintype "power_in"))
      (node (ref "U1") (pin "AC14") (pinfunction "VCCPT_AC14") (pintype "power_in"))
      (node (ref "U1") (pin "AC16") (pinfunction "VCCPT_AC16") (pintype "power_in"))
      (node (ref "U1") (pin "AC17") (pinfunction "VCCPT_AC17") (pintype "power_in"))
      (node (ref "U1") (pin "AC19") (pinfunction "VCCPT_AC19") (pintype "power_in"))
      (node (ref "U1") (pin "AC21") (pinfunction "VCCPT_AC21") (pintype "power_in"))
      (node (ref "U1") (pin "AD27") (pinfunction "VCCH_GXBL_AD27") (pintype "power_in"))
      (node (ref "U1") (pin "AE18") (pinfunction "VCCBAT_AE18") (pintype "power_in"))
      (node (ref "U1") (pin "AH27") (pinfunction "VCCH_GXBL_AH27") (pintype "power_in"))
      (node (ref "U1") (pin "AM27") (pinfunction "VCCH_GXBL_AM27") (pintype "power_in"))
      (node (ref "U1") (pin "D27") (pinfunction "VCCH_GXBL_D27") (pintype "power_in"))
      (node (ref "U1") (pin "H27") (pinfunction "VCCH_GXBL_H27") (pintype "power_in"))
      (node (ref "U1") (pin "M27") (pinfunction "VCCH_GXBL_M27") (pintype "power_in"))
      (node (ref "U1") (pin "T27") (pinfunction "VCCH_GXBL_T27") (pintype "power_in"))
      (node (ref "U1") (pin "U15") (pinfunction "VCCPT_U15") (pintype "power_in"))
      (node (ref "U1") (pin "U16") (pinfunction "VCCPT_U16") (pintype "power_in"))
      (node (ref "U1") (pin "U17") (pinfunction "VCCPT_U17") (pintype "power_in"))
      (node (ref "U1") (pin "U20") (pinfunction "VCCPT_U20") (pintype "power_in"))
      (node (ref "U1") (pin "U21") (pinfunction "VCCPT_U21") (pintype "power_in"))
      (node (ref "U1") (pin "U22") (pinfunction "VCCPT_U22") (pintype "power_in"))
      (node (ref "U1") (pin "W19") (pinfunction "VCCA_PLL_W19") (pintype "power_in"))
      (node (ref "U1") (pin "Y27") (pinfunction "VCCH_GXBL_Y27") (pintype "power_in"))
    )
    (net (code "26") (name "VCCIOREF_HPS") (class "Default")
      (node (ref "U1") (pin "N16") (pinfunction "VCCIOREF_HPS_N16") (pintype "power_in"))
    )
    (net (code "27") (name "VCCIO_HPS") (class "Default")
      (node (ref "U1") (pin "M16") (pinfunction "VCCIO_HPS_M16") (pintype "power_in"))
    )
    (net (code "28") (name "VDD_DDR") (class "Default")
      (node (ref "R197") (pin "1") (pinfunction "1_1") (pintype "passive"))
      (node (ref "R198") (pin "1") (pinfunction "1_1") (pintype "passive"))
      (node (ref "R200") (pin "1") (pinfunction "1_1") (pintype "passive"))
      (node (ref "R201") (pin "1") (pinfunction "1_1") (pintype "passive"))
      (node (ref "R202") (pin "1") (pinfunction "1_1") (pintype "passive"))
      (node (ref "U1") (pin "AA6") (pinfunction "VCCIO3D_AA6") (pintype "power_in"))
      (node (ref "U1") (pin "AC5") (pinfunction "VCCIO3D_AC5") (pintype "power_in"))
      (node (ref "U1") (pin "AD7") (pinfunction "VCCIO3C_AD7") (pintype "power_in"))
      (node (ref "U1") (pin "AG8") (pinfunction "VCCIO3C_AG8") (pintype "power_in"))
      (node (ref "U1") (pin "AH5") (pinfunction "VCCIO3C_AH5") (pintype "power_in"))
      (node (ref "U1") (pin "AK24") (pinfunction "VCCIO2J_AK24") (pintype "power_in"))
      (node (ref "U1") (pin "AK9") (pinfunction "VCCIO3B_AK9") (pintype "power_in"))
      (node (ref "U1") (pin "AL6") (pinfunction "VCCIO3B_AL6") (pintype "power_in"))
      (node (ref "U1") (pin "AM8") (pinfunction "VCCIO3B_AM8") (pintype "power_in"))
      (node (ref "U1") (pin "AN25") (pinfunction "VCCIO2J_AN25") (pintype "power_in"))
      (node (ref "U1") (pin "AR24") (pinfunction "VCCIO2J_AR24") (pintype "power_in"))
      (node (ref "U1") (pin "E24") (pinfunction "VCCIO2K_E24") (pintype "power_in"))
      (node (ref "U1") (pin "H25") (pinfunction "VCCIO2K_H25") (pintype "power_in"))
      (node (ref "U1") (pin "K24") (pinfunction "VCCIO2K_K24") (pintype "power_in"))
      (node (ref "U1") (pin "Y4") (pinfunction "VCCIO3D_Y4") (pintype "power_in"))
    )
    (net (code "29") (name "unconnected-(U13-DNC-Pad1)") (class "Default")
      (node (ref "U13") (pin "1") (pinfunction "DNC_1") (pintype "passive"))
    )
    (net (code "30") (name "unconnected-(U13-DNC-Pad2)") (class "Default")
      (node (ref "U13") (pin "2") (pinfunction "DNC_2") (pintype "passive"))
    )
    (net (code "31") (name "unconnected-(U13-DNC-Pad3)") (class "Default")
      (node (ref "U13") (pin "3") (pinfunction "DNC_3") (pintype "passive"))
    )
    (net (code "32") (name "unconnected-(U13-DNC-Pad7)") (class "Default")
      (node (ref "U13") (pin "7") (pinfunction "DNC_7") (pintype "passive"))
    )
    (net (code "33") (name "unconnected-(U13-DNC-Pad8)") (class "Default")
      (node (ref "U13") (pin "8") (pinfunction "DNC_8") (pintype "passive"))
    )
  )
)
